# ForAtmega328P.net
KiCad netlist of a schematic drawn in Altium Designer
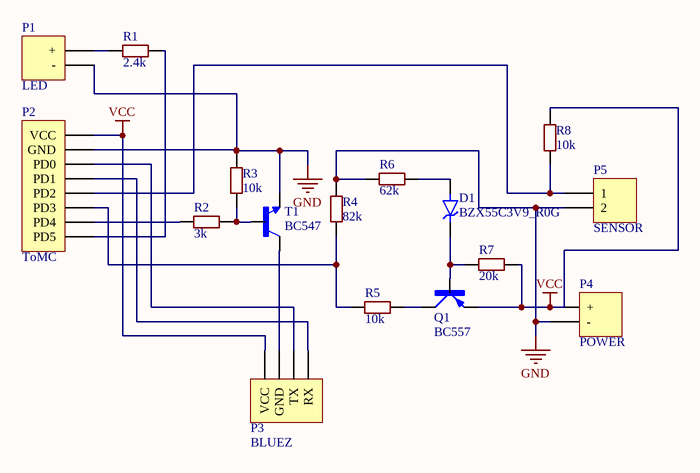
[diagram p0: ForAtmega328P.SchDoc]

(export (version "E")
  (design (tool "Eeschema 10.0.6"))
  (components
    (comp (ref "D1")
      (value "BZX55C3V9_R0G")
      (footprint "DIOAD928W47L399D179")
      (fields (field (name "MP") "altium_native_batch"))
      (libsource (lib "BZX55C3V9_R0G") (part "BZX55C3V9_R0G"))
    )
    (comp (ref "P1")
      (value "LED")
      (footprint "HDR1X2")
      (description "Header, 2-Pin")
      (fields (field (name "PUBLISHER") "Altium Limited"))
      (libsource (lib "Miscellaneous Connectors") (part "Header 2"))
    )
    (comp (ref "P2")
      (value "ToMC")
      (footprint "HDR1X8")
      (description "Header, 8-Pin")
      (fields (field (name "PUBLISHER") "Altium Limited"))
      (libsource (lib "Miscellaneous Connectors") (part "Header 8"))
    )
    (comp (ref "P3")
      (value "BLUEZ")
      (footprint "HDR1X4")
      (description "Header, 4-Pin")
      (fields (field (name "PUBLISHER") "Altium Limited"))
      (libsource (lib "Miscellaneous Connectors") (part "Header 4"))
    )
    (comp (ref "P4")
      (value "POWER")
      (footprint "HDR1X2")
      (description "Header, 2-Pin")
      (fields (field (name "PUBLISHER") "Altium Limited"))
      (libsource (lib "") (part "Header 2_2"))
    )
    (comp (ref "P5")
      (value "SENSOR")
      (footprint "HDR1X2")
      (description "Header, 2-Pin")
      (fields (field (name "PUBLISHER") "Altium Limited"))
      (libsource (lib "") (part "Header 2_1"))
    )
    (comp (ref "Q1")
      (value "BC557")
      (footprint "SOT54A")
      (description "Bipolar (BJT) Transistor PNP 45 V 100 mA 320MHz 625 mW Through Hole TO-92 (TO-226)")
      (fields (field (name "MF") "ON Semiconductor"))
      (libsource (lib "BC557") (part "BC557"))
    )
    (comp (ref "R1") (value "2.4k") (footprint "Res") (libsource (lib "") (part "Res_1")))
    (comp (ref "R2") (value "3k") (footprint "Res") (libsource (lib "") (part "Res_1")))
    (comp (ref "R3") (value "10k") (footprint "Res") (libsource (lib "Res") (part "Res")))
    (comp (ref "R4") (value "82k") (footprint "Res") (libsource (lib "Res") (part "Res")))
    (comp (ref "R5") (value "10k") (footprint "Res") (libsource (lib "") (part "Res_1")))
    (comp (ref "R6") (value "62k") (footprint "Res") (libsource (lib "") (part "Res_1")))
    (comp (ref "R7") (value "20k") (footprint "Res") (libsource (lib "") (part "Res_1")))
    (comp (ref "R8") (value "10k") (footprint "Res") (libsource (lib "") (part "Res_2")))
    (comp (ref "T1")
      (value "BC547")
      (footprint "TO92")
      (description "Trans GP BJT NPN 45V 0.1A 500mW 3-Pin TO-92 T/R")
      (fields (field (name "MF") "ON Semiconductor"))
      (libsource (lib "BC547") (part "BC547"))
    )
  )
  (nets
    (net (code "1") (name "GND") (class "Default")
      (node (ref "P1") (pin "2") (pinfunction "-_2") (pintype "passive"))
      (node (ref "P2") (pin "2") (pinfunction "GND_2") (pintype "passive"))
      (node (ref "P4") (pin "2") (pinfunction "-_2") (pintype "passive"))
      (node (ref "P5") (pin "2") (pinfunction "2_2") (pintype "passive"))
      (node (ref "R3") (pin "2") (pinfunction "2_2") (pintype "passive"))
      (node (ref "R4") (pin "2") (pinfunction "2_2") (pintype "passive"))
      (node (ref "R6") (pin "1") (pinfunction "1_1") (pintype "passive"))
      (node (ref "T1") (pin "1") (pinfunction "E_1") (pintype "passive"))
    )
    (net (code "2") (name "Net-(D1-K)") (class "Default")
      (node (ref "D1") (pin "C") (pinfunction "K_C") (pintype "passive"))
      (node (ref "Q1") (pin "B") (pinfunction "B_B") (pintype "passive"))
      (node (ref "R7") (pin "1") (pinfunction "1_1") (pintype "passive"))
    )
    (net (code "3") (name "Net-(D1-PadA)") (class "Default")
      (node (ref "D1") (pin "A") (pinfunction "A_A") (pintype "passive"))
      (node (ref "R6") (pin "2") (pinfunction "2_2") (pintype "passive"))
    )
    (net (code "4") (name "Net-(P1-+)") (class "Default")
      (node (ref "P1") (pin "1") (pinfunction "+_1") (pintype "passive"))
      (node (ref "R1") (pin "1") (pinfunction "1_1") (pintype "passive"))
    )
    (net (code "5") (name "Net-(P2-PD0)") (class "Default")
      (node (ref "P2") (pin "3") (pinfunction "PD0_3") (pintype "passive"))
      (node (ref "P3") (pin "3") (pinfunction "TX_3") (pintype "passive"))
    )
    (net (code "6") (name "Net-(P2-PD1)") (class "Default")
      (node (ref "P2") (pin "4") (pinfunction "PD1_4") (pintype "passive"))
      (node (ref "P3") (pin "4") (pinfunction "RX_4") (pintype "passive"))
    )
    (net (code "7") (name "Net-(P2-PD2)") (class "Default")
      (node (ref "P2") (pin "5") (pinfunction "PD2_5") (pintype "passive"))
      (node (ref "P5") (pin "1") (pinfunction "1_1") (pintype "passive"))
      (node (ref "R8") (pin "2") (pinfunction "2_2") (pintype "passive"))
    )
    (net (code "8") (name "Net-(P2-PD3)") (class "Default")
      (node (ref "P2") (pin "6") (pinfunction "PD3_6") (pintype "passive"))
      (node (ref "R4") (pin "1") (pinfunction "1_1") (pintype "passive"))
      (node (ref "R5") (pin "1") (pinfunction "1_1") (pintype "passive"))
    )
    (net (code "9") (name "Net-(P2-PD4)") (class "Default")
      (node (ref "P2") (pin "7") (pinfunction "PD4_7") (pintype "passive"))
      (node (ref "R2") (pin "1") (pinfunction "1_1") (pintype "passive"))
    )
    (net (code "10") (name "Net-(P2-PD5)") (class "Default")
      (node (ref "P2") (pin "8") (pinfunction "PD5_8") (pintype "passive"))
      (node (ref "R1") (pin "2") (pinfunction "2_2") (pintype "passive"))
    )
    (net (code "11") (name "Net-(P3-GND)") (class "Default")
      (node (ref "P3") (pin "2") (pinfunction "GND_2") (pintype "passive"))
      (node (ref "T1") (pin "3") (pinfunction "C_3") (pintype "passive"))
    )
    (net (code "12") (name "Net-(Q1-PadC)") (class "Default")
      (node (ref "Q1") (pin "C") (pinfunction "C_C") (pintype "passive"))
      (node (ref "R5") (pin "2") (pinfunction "2_2") (pintype "passive"))
    )
    (net (code "13") (name "Net-(T1-B)") (class "Default")
      (node (ref "R2") (pin "2") (pinfunction "2_2") (pintype "passive"))
      (node (ref "R3") (pin "1") (pinfunction "1_1") (pintype "passive"))
      (node (ref "T1") (pin "2") (pinfunction "B_2") (pintype "passive"))
    )
    (net (code "14") (name "VCC") (class "Default")
      (node (ref "P2") (pin "1") (pinfunction "VCC_1") (pintype "passive"))
      (node (ref "P3") (pin "1") (pinfunction "VCC_1") (pintype "passive"))
      (node (ref "P4") (pin "1") (pinfunction "+_1") (pintype "passive"))
      (node (ref "Q1") (pin "E") (pinfunction "E_E") (pintype "passive"))
      (node (ref "R7") (pin "2") (pinfunction "2_2") (pintype "passive"))
      (node (ref "R8") (pin "1") (pinfunction "1_1") (pintype "passive"))
    )
  )
)
